# Sheet1.net
KiCad netlist of a schematic drawn in Altium Designer
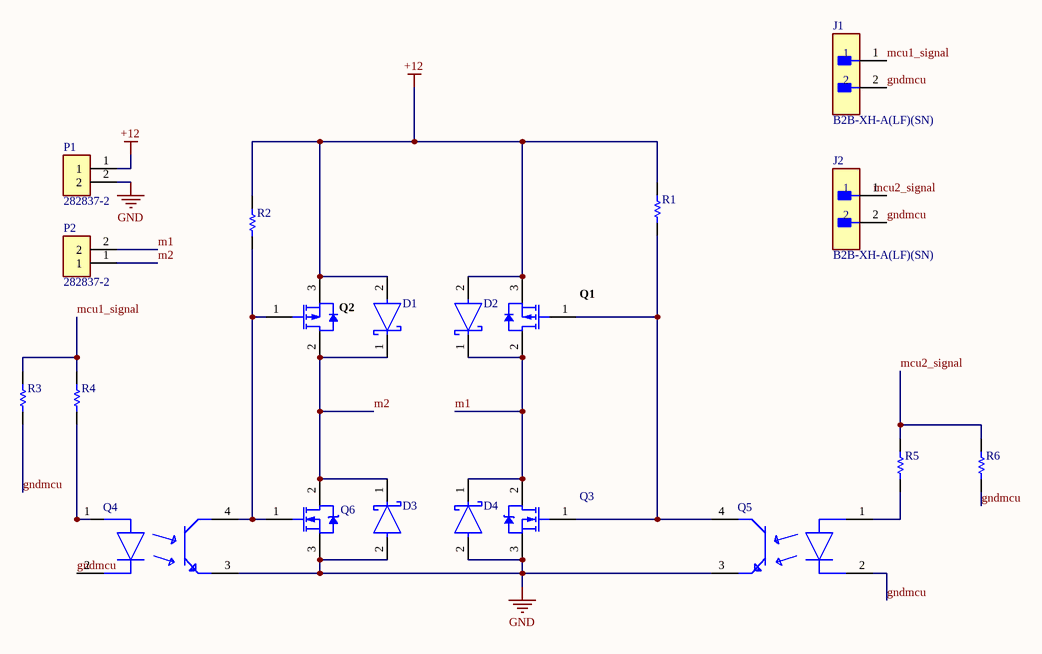
[diagram p0: Sheet1.SchDoc]

(export (version "E")
  (design (tool "Eeschema 10.0.6"))
  (components
    (comp (ref "D1")
      (value "1N5822-E3/54")
      (footprint "FP-1N5822-E3-54-MFG")
      (description "DIODE SCHOTTKY 40V 3A DO201AD")
      (fields
        (field (name "OCTOPART") "https://octopart.com/1n5822-e3%2F54-vishay-39548309")
        (field (name "MANUFACTURER") "Vishay")
      )
      (libsource (lib "Altium Content Vault") (part "1d6ec82d83fb6aee721767c19dac4b9"))
    )
    (comp (ref "D2")
      (value "1N5822-E3/54")
      (footprint "FP-1N5822-E3-54-MFG")
      (description "DIODE SCHOTTKY 40V 3A DO201AD")
      (fields
        (field (name "OCTOPART") "https://octopart.com/1n5822-e3%2F54-vishay-39548309")
        (field (name "MANUFACTURER") "Vishay")
      )
      (libsource (lib "Altium Content Vault") (part "1d6ec82d83fb6aee721767c19dac4b9"))
    )
    (comp (ref "D3")
      (value "1N5822-E3/54")
      (footprint "FP-1N5822-E3-54-MFG")
      (description "DIODE SCHOTTKY 40V 3A DO201AD")
      (fields
        (field (name "OCTOPART") "https://octopart.com/1n5822-e3%2F54-vishay-39548309")
        (field (name "MANUFACTURER") "Vishay")
      )
      (libsource (lib "Altium Content Vault") (part "1d6ec82d83fb6aee721767c19dac4b9"))
    )
    (comp (ref "D4")
      (value "1N5822-E3/54")
      (footprint "FP-1N5822-E3-54-MFG")
      (description "DIODE SCHOTTKY 40V 3A DO201AD")
      (fields
        (field (name "OCTOPART") "https://octopart.com/1n5822-e3%2F54-vishay-39548309")
        (field (name "MANUFACTURER") "Vishay")
      )
      (libsource (lib "Altium Content Vault") (part "1d6ec82d83fb6aee721767c19dac4b9"))
    )
    (comp (ref "J1")
      (value "B2B-XH-A(LF)(SN)")
      (footprint "FP-B2B-XH-A_LF_SN-MFG")
      (description "CONN HEADER VERT 2POS 2.5MM")
      (libsource (lib "Altium Content Vault") (part "3bc925449376181038e59eaffc5286c"))
    )
    (comp (ref "J2")
      (value "B2B-XH-A(LF)(SN)")
      (footprint "FP-B2B-XH-A_LF_SN-MFG")
      (description "CONN HEADER VERT 2POS 2.5MM")
      (libsource (lib "Altium Content Vault") (part "3bc925449376181038e59eaffc5286c"))
    )
    (comp (ref "P1")
      (value "282837-2")
      (footprint "TE_282837-2")
      (fields (field (name "MF") "TE Connectivity"))
      (libsource (lib "") (part "282837-2_1"))
    )
    (comp (ref "P2")
      (value "282837-2")
      (footprint "TE_282837-2")
      (fields (field (name "MF") "TE Connectivity"))
      (libsource (lib "282837-2 (1)") (part "282837-2"))
    )
    (comp (ref "Q1")
      (value "FQP27P06")
      (footprint "FAIR-TO-220-3")
      (description "P-Channel QFET(R) MOSFET, -60 V, -27 A, -55 to 175 degC, 3-Pin TO-220, RoHS, Tube")
      (fields (field (name "MANUFACTURER") "Fairchild"))
      (libsource (lib "Altium Content Vault") (part "PEMOS-GDS-3"))
    )
    (comp (ref "Q2")
      (value "FQP27P06")
      (footprint "FAIR-TO-220-3")
      (description "P-Channel QFET(R) MOSFET, -60 V, -27 A, -55 to 175 degC, 3-Pin TO-220, RoHS, Tube")
      (fields (field (name "MANUFACTURER") "Fairchild"))
      (libsource (lib "Altium Content Vault") (part "PEMOS-GDS-3"))
    )
    (comp (ref "Q3")
      (value "IRLB3034PBF")
      (footprint "INF-PG-TO-220AB")
      (description "Mosfet N-Channel, 40 V, 195 A, -55 to 175 degC, 3-Pin TO-220AB, RoHS, Tube")
      (fields (field (name "MANUFACTURER") "International Rectifier"))
      (libsource (lib "Altium Content Vault") (part "NEMOS-GDS-3_B"))
    )
    (comp (ref "Q4")
      (value "PC817X4NIP0F")
      (footprint "FP-PC817X4NIP0F-MFG")
      (description "Optocoupler DC-IN 1-CH Transistor DC-OUT 4-Pin PDIP SMD")
      (fields (field (name "OCTOPART") "https://octopart.com/pc817x4nip0f-sharp-20650453"))
      (libsource (lib "Altium Content Vault") (part "8ff5844b63c0dea0057760e9ee25456"))
    )
    (comp (ref "Q5")
      (value "PC817X4NIP0F")
      (footprint "FP-PC817X4NIP0F-MFG")
      (description "Optocoupler DC-IN 1-CH Transistor DC-OUT 4-Pin PDIP SMD")
      (fields (field (name "OCTOPART") "https://octopart.com/pc817x4nip0f-sharp-20650453"))
      (libsource (lib "Altium Content Vault") (part "8ff5844b63c0dea0057760e9ee25456"))
    )
    (comp (ref "Q6")
      (value "IRLB3034PBF")
      (footprint "INF-PG-TO-220AB")
      (description "Mosfet N-Channel, 40 V, 195 A, -55 to 175 degC, 3-Pin TO-220AB, RoHS, Tube")
      (fields (field (name "MANUFACTURER") "International Rectifier"))
      (libsource (lib "Altium Content Vault") (part "NEMOS-GDS-3_B"))
    )
    (comp (ref "R1")
      (value "MFR-25FBF5210K")
      (footprint "RESA60-630X240")
      (description "Axial Resistor, 10 KOhm, +/- 1%, 0.25 W, -55 to 155 degC, 2-Pin THD, RoHS, Bulk")
      (fields (field (name "TOLERANCE") "1%") (field (name "MANUFACTURER") "Yageo"))
      (libsource (lib "Altium Content Vault") (part "RES-2"))
    )
    (comp (ref "R2")
      (value "MFR-25FBF5210K")
      (footprint "RESA60-630X240")
      (description "Axial Resistor, 10 KOhm, +/- 1%, 0.25 W, -55 to 155 degC, 2-Pin THD, RoHS, Bulk")
      (fields (field (name "TOLERANCE") "1%") (field (name "MANUFACTURER") "Yageo"))
      (libsource (lib "Altium Content Vault") (part "RES-2"))
    )
    (comp (ref "R3")
      (value "MFR-25FBF5210K")
      (footprint "RESA60-630X240")
      (description "Axial Resistor, 10 KOhm, +/- 1%, 0.25 W, -55 to 155 degC, 2-Pin THD, RoHS, Bulk")
      (fields (field (name "TOLERANCE") "1%") (field (name "MANUFACTURER") "Yageo"))
      (libsource (lib "Altium Content Vault") (part "RES-2"))
    )
    (comp (ref "R4")
      (value "MFR-25FBF52470Ohm")
      (footprint "RESA60-630X240")
      (description "Axial Resistor, 470 Ohm, +/- 1%, 0.25 W, -55 to 155 degC, 2-Pin THD, RoHS, Bulk")
      (fields (field (name "TOLERANCE") "1%") (field (name "MANUFACTURER") "Yageo"))
      (libsource (lib "Altium Content Vault") (part "RES-2"))
    )
    (comp (ref "R5")
      (value "MFR-25FBF52470Ohm")
      (footprint "RESA60-630X240")
      (description "Axial Resistor, 470 Ohm, +/- 1%, 0.25 W, -55 to 155 degC, 2-Pin THD, RoHS, Bulk")
      (fields (field (name "TOLERANCE") "1%") (field (name "MANUFACTURER") "Yageo"))
      (libsource (lib "Altium Content Vault") (part "RES-2"))
    )
    (comp (ref "R6")
      (value "MFR-25FBF5210K")
      (footprint "RESA60-630X240")
      (description "Axial Resistor, 10 KOhm, +/- 1%, 0.25 W, -55 to 155 degC, 2-Pin THD, RoHS, Bulk")
      (fields (field (name "TOLERANCE") "1%") (field (name "MANUFACTURER") "Yageo"))
      (libsource (lib "Altium Content Vault") (part "RES-2"))
    )
  )
  (nets
    (net (code "1") (name "+12") (class "Default")
      (node (ref "D1") (pin "2") (pinfunction "A_2") (pintype "passive"))
      (node (ref "D2") (pin "2") (pinfunction "A_2") (pintype "passive"))
      (node (ref "P1") (pin "1") (pinfunction "1_1") (pintype "passive"))
      (node (ref "Q1") (pin "3") (pinfunction "S_3") (pintype "passive"))
      (node (ref "Q2") (pin "3") (pinfunction "S_3") (pintype "passive"))
      (node (ref "R1") (pin "2") (pinfunction "2_2") (pintype "passive"))
      (node (ref "R2") (pin "2") (pinfunction "2_2") (pintype "passive"))
    )
    (net (code "2") (name "/gndmcu") (class "Default")
      (node (ref "J1") (pin "2") (pinfunction "2_2") (pintype "passive"))
      (node (ref "J2") (pin "2") (pinfunction "2_2") (pintype "passive"))
      (node (ref "Q4") (pin "2") (pinfunction "C_2") (pintype "passive"))
      (node (ref "Q5") (pin "2") (pinfunction "C_2") (pintype "passive"))
      (node (ref "R3") (pin "1") (pinfunction "1_1") (pintype "passive"))
      (node (ref "R6") (pin "1") (pinfunction "1_1") (pintype "passive"))
    )
    (net (code "3") (name "/m1") (class "Default")
      (node (ref "D2") (pin "1") (pinfunction "C_1") (pintype "passive"))
      (node (ref "D4") (pin "1") (pinfunction "C_1") (pintype "passive"))
      (node (ref "P2") (pin "2") (pinfunction "2_2") (pintype "passive"))
      (node (ref "Q1") (pin "2") (pinfunction "D_2") (pintype "passive"))
      (node (ref "Q3") (pin "2") (pinfunction "D_2") (pintype "passive"))
    )
    (net (code "4") (name "/m2") (class "Default")
      (node (ref "D1") (pin "1") (pinfunction "C_1") (pintype "passive"))
      (node (ref "D3") (pin "1") (pinfunction "C_1") (pintype "passive"))
      (node (ref "P2") (pin "1") (pinfunction "1_1") (pintype "passive"))
      (node (ref "Q2") (pin "2") (pinfunction "D_2") (pintype "passive"))
      (node (ref "Q6") (pin "2") (pinfunction "D_2") (pintype "passive"))
    )
    (net (code "5") (name "/mcu1_signal") (class "Default")
      (node (ref "J1") (pin "1") (pinfunction "1_1") (pintype "passive"))
      (node (ref "R3") (pin "2") (pinfunction "2_2") (pintype "passive"))
      (node (ref "R4") (pin "2") (pinfunction "2_2") (pintype "passive"))
    )
    (net (code "6") (name "/mcu2_signal") (class "Default")
      (node (ref "R5") (pin "2") (pinfunction "2_2") (pintype "passive"))
      (node (ref "R6") (pin "2") (pinfunction "2_2") (pintype "passive"))
    )
    (net (code "7") (name "GND") (class "Default")
      (node (ref "D3") (pin "2") (pinfunction "A_2") (pintype "passive"))
      (node (ref "D4") (pin "2") (pinfunction "A_2") (pintype "passive"))
      (node (ref "P1") (pin "2") (pinfunction "2_2") (pintype "passive"))
      (node (ref "Q3") (pin "3") (pinfunction "S_3") (pintype "passive"))
      (node (ref "Q4") (pin "3") (pinfunction "E_3") (pintype "passive"))
      (node (ref "Q5") (pin "3") (pinfunction "E_3") (pintype "passive"))
      (node (ref "Q6") (pin "3") (pinfunction "S_3") (pintype "passive"))
    )
    (net (code "8") (name "Net-(Q1-G)") (class "Default")
      (node (ref "Q1") (pin "1") (pinfunction "G_1") (pintype "passive"))
      (node (ref "Q3") (pin "1") (pinfunction "G_1") (pintype "passive"))
      (node (ref "Q5") (pin "4") (pinfunction "C_4") (pintype "passive"))
      (node (ref "R1") (pin "1") (pinfunction "1_1") (pintype "passive"))
    )
    (net (code "9") (name "Net-(Q2-G)") (class "Default")
      (node (ref "Q2") (pin "1") (pinfunction "G_1") (pintype "passive"))
      (node (ref "Q4") (pin "4") (pinfunction "C_4") (pintype "passive"))
      (node (ref "Q6") (pin "1") (pinfunction "G_1") (pintype "passive"))
      (node (ref "R2") (pin "1") (pinfunction "1_1") (pintype "passive"))
    )
    (net (code "10") (name "Net-(Q4-A)") (class "Default")
      (node (ref "Q4") (pin "1") (pinfunction "A_1") (pintype "passive"))
      (node (ref "R4") (pin "1") (pinfunction "1_1") (pintype "passive"))
    )
    (net (code "11") (name "Net-(Q5-A)") (class "Default")
      (node (ref "Q5") (pin "1") (pinfunction "A_1") (pintype "passive"))
      (node (ref "R5") (pin "1") (pinfunction "1_1") (pintype "passive"))
    )
    (net (code "12") (name "unconnected-(J2-Pad1)") (class "Default")
      (node (ref "J2") (pin "1") (pinfunction "1_1") (pintype "passive"))
    )
  )
)
